# dynext_v1_1.net
KiCad netlist of a schematic drawn in EAGLE
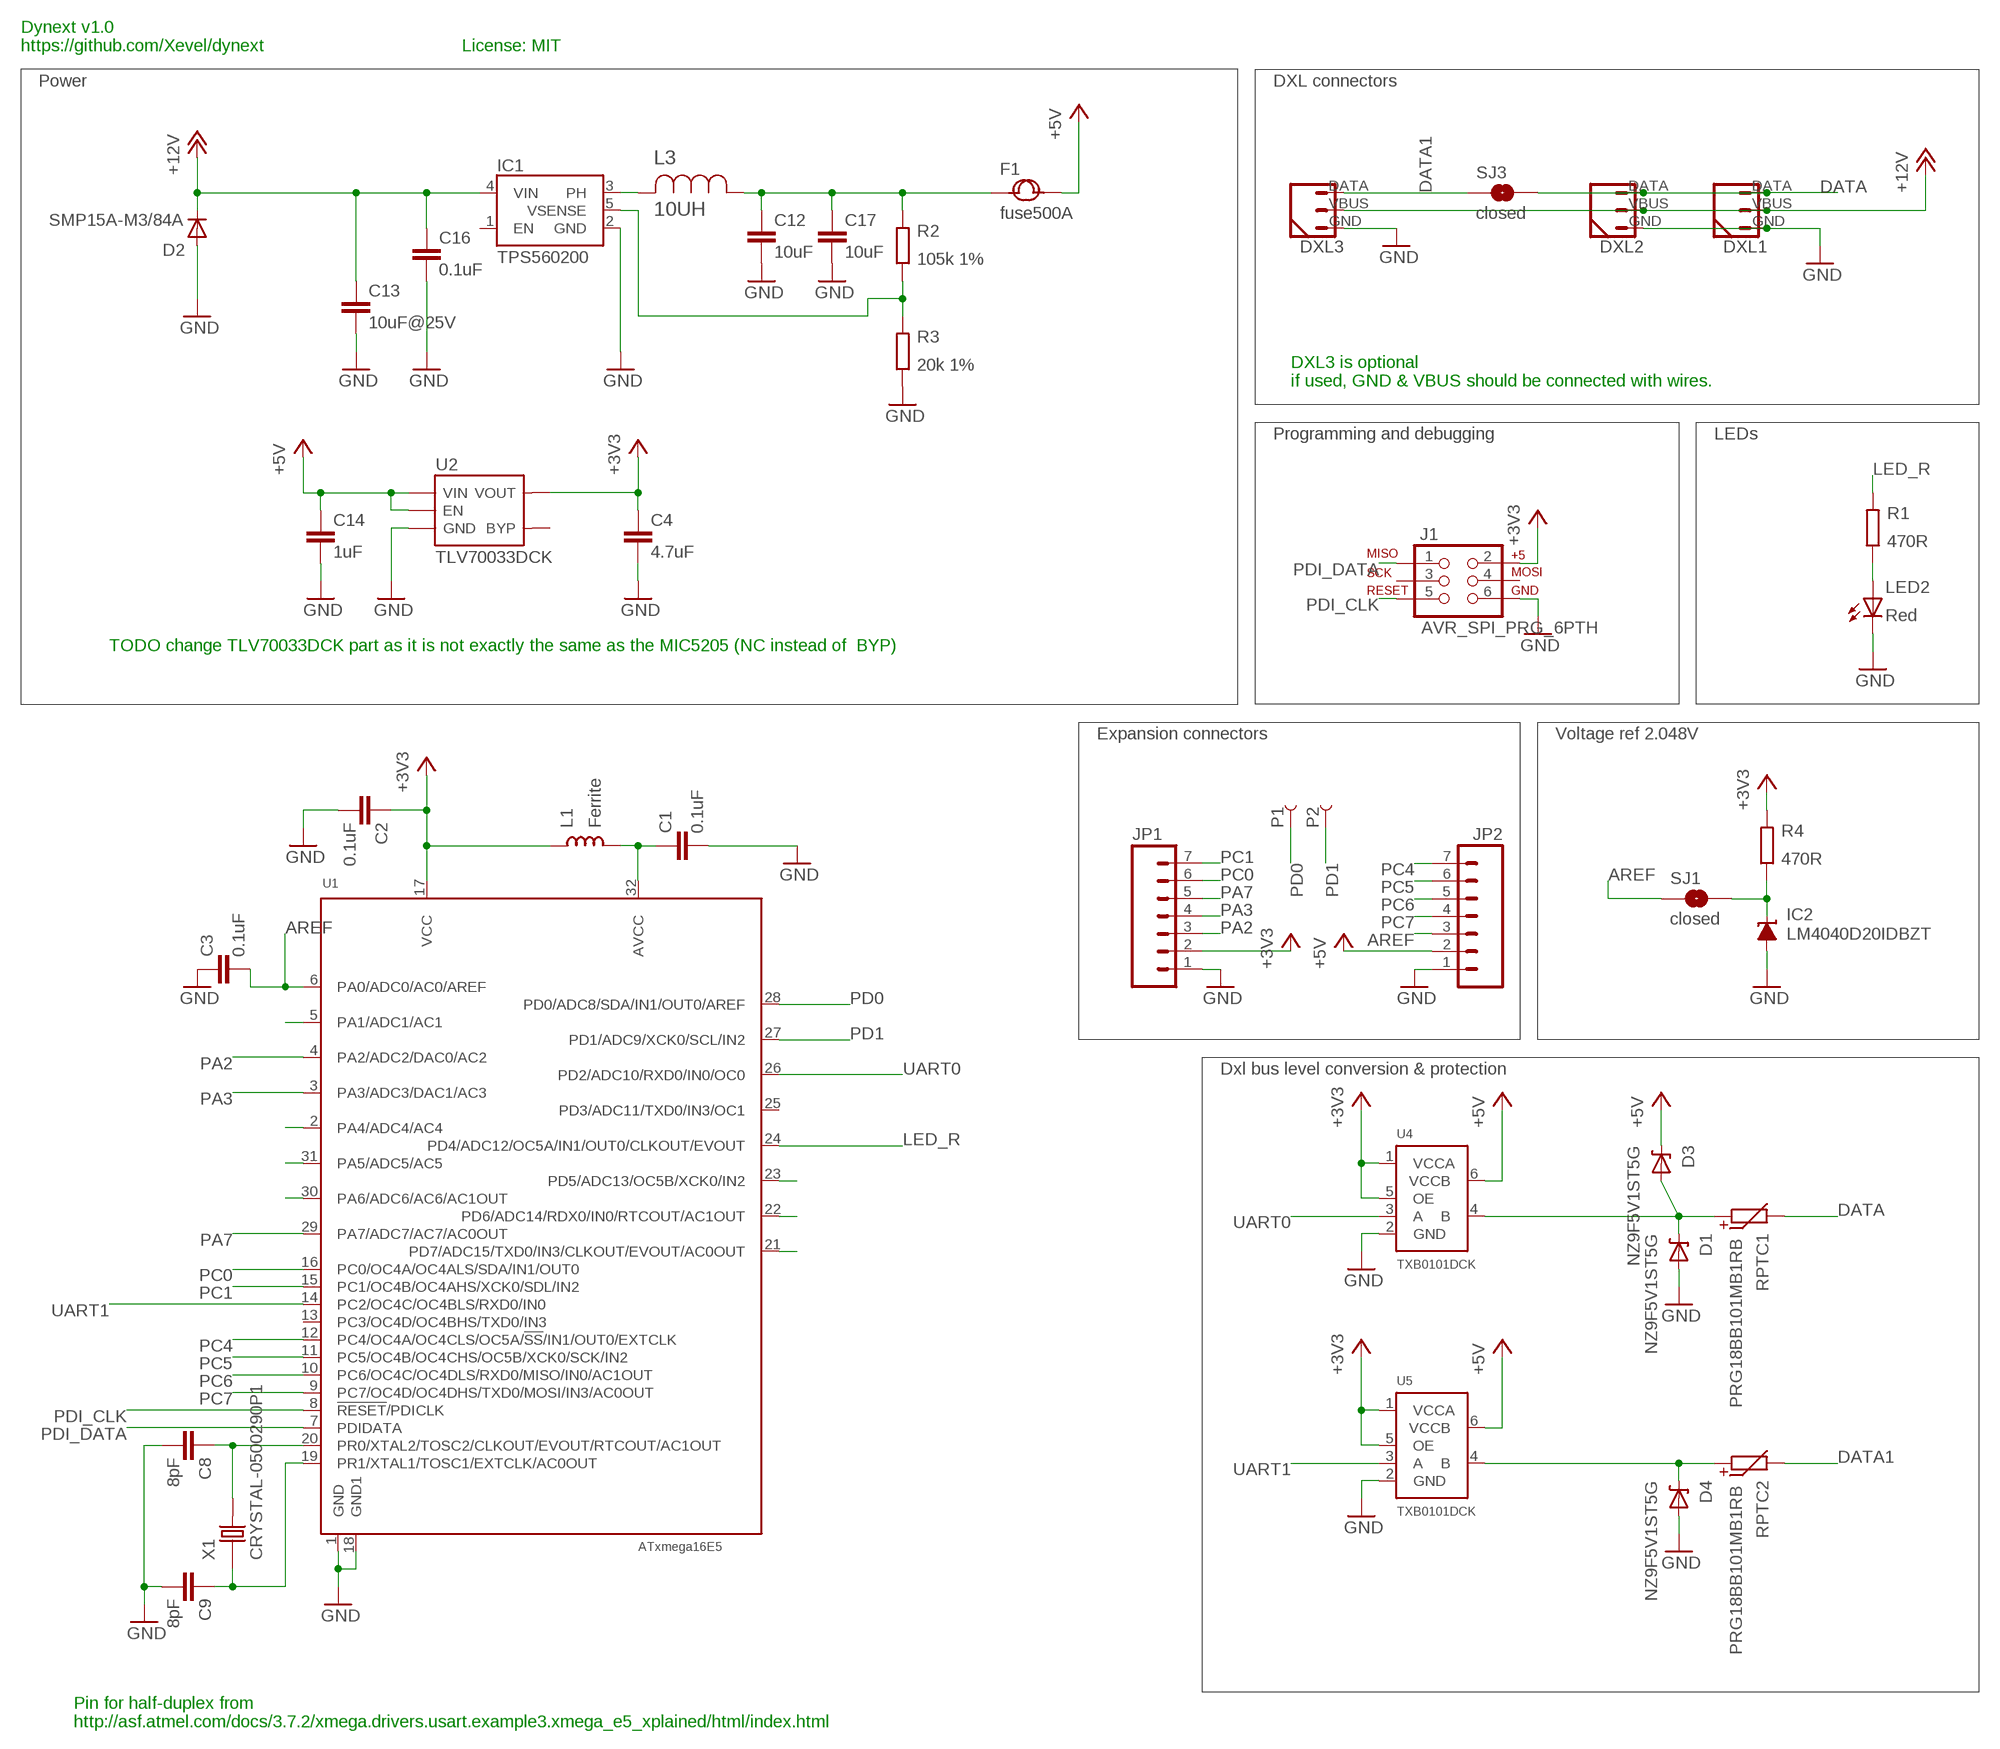
[diagram p0: schematic, sheet 1]

(export (version "E")
  (design (tool "Eeschema 10.0.6"))
  (components
    (comp (ref "C1")
      (value "0.1uF")
      (footprint "eagle-import:0402_N")
      (libsource (lib "eagle-import") (part "C0402"))
    )
    (comp (ref "C2")
      (value "0.1uF")
      (footprint "eagle-import:0402_N")
      (libsource (lib "eagle-import") (part "C0402"))
    )
    (comp (ref "C3")
      (value "0.1uF")
      (footprint "eagle-import:0402_N")
      (libsource (lib "eagle-import") (part "C0402"))
    )
    (comp (ref "C4")
      (value "4.7uF")
      (footprint "eagle-import:0603_N")
      (libsource (lib "eagle-import") (part "C0603"))
    )
    (comp (ref "C8")
      (value "8pF")
      (footprint "eagle-import:0402_N")
      (libsource (lib "eagle-import") (part "C0402"))
    )
    (comp (ref "C9")
      (value "8pF")
      (footprint "eagle-import:0402_N")
      (libsource (lib "eagle-import") (part "C0402"))
    )
    (comp (ref "C12")
      (value "10uF")
      (footprint "eagle-import:0805_N")
      (libsource (lib "eagle-import") (part "C0805"))
    )
    (comp (ref "C13")
      (value "10uF@25V")
      (footprint "eagle-import:0805_N")
      (libsource (lib "eagle-import") (part "C0805"))
    )
    (comp (ref "C14")
      (value "1uF")
      (footprint "eagle-import:0402_N")
      (libsource (lib "eagle-import") (part "C0402"))
    )
    (comp (ref "C16")
      (value "0.1uF")
      (footprint "eagle-import:0402_N")
      (libsource (lib "eagle-import") (part "C0402"))
    )
    (comp (ref "C17")
      (value "10uF")
      (footprint "eagle-import:0805_N")
      (libsource (lib "eagle-import") (part "C0805"))
    )
    (comp (ref "D1")
      (value "NZ9F5V1ST5G")
      (footprint "eagle-import:SOD-923_N")
      (libsource (lib "eagle-import") (part "DIODE_ZENER-923"))
    )
    (comp (ref "D2")
      (value "SMP15A-M3/84A")
      (footprint "eagle-import:DO-220AA")
      (libsource (lib "eagle-import") (part "DIODE-SMP"))
    )
    (comp (ref "D3")
      (value "NZ9F5V1ST5G")
      (footprint "eagle-import:SOD-923_N")
      (libsource (lib "eagle-import") (part "DIODE_ZENER-923"))
    )
    (comp (ref "D4")
      (value "NZ9F5V1ST5G")
      (footprint "eagle-import:SOD-923_N")
      (libsource (lib "eagle-import") (part "DIODE_ZENER-923"))
    )
    (comp (ref "DXL1")
      (value "DYNAMIXEL_3POS-T")
      (footprint "eagle-import:DYNAMIXEL_3POS_TOP")
      (libsource (lib "eagle-import") (part "DYNAMIXEL_3POS-T"))
    )
    (comp (ref "DXL2")
      (value "DYNAMIXEL_3POS-T")
      (footprint "eagle-import:DYNAMIXEL_3POS_TOP")
      (libsource (lib "eagle-import") (part "DYNAMIXEL_3POS-T"))
    )
    (comp (ref "DXL3")
      (value "DYNAMIXEL_3POS-R")
      (footprint "eagle-import:DYNAMIXEL_3POS_RIGHT")
      (libsource (lib "eagle-import") (part "DYNAMIXEL_3POS-R"))
    )
    (comp (ref "F1")
      (value "fuse500A")
      (footprint "eagle-import:F1206")
      (libsource (lib "eagle-import") (part "FUSE-1206"))
    )
    (comp (ref "IC1")
      (value "TPS560200")
      (footprint "eagle-import:SOT-23-5_N")
      (libsource (lib "eagle-import") (part "IC_TPS560200"))
    )
    (comp (ref "IC2")
      (value "LM4040D20IDBZT")
      (footprint "eagle-import:DBZ_R-PDSO-G3")
      (fields (field (name "MPN") "LM4041A12IDBZR"))
      (libsource (lib "eagle-import") (part "LM4041DBZA12"))
    )
    (comp (ref "J1")
      (value "AVR_SPI_PRG_6PTH")
      (footprint "eagle-import:2X3")
      (libsource (lib "eagle-import") (part "AVR_SPI_PRG_6PTH"))
    )
    (comp (ref "JP1")
      (value "M07")
      (footprint "eagle-import:1X07")
      (libsource (lib "eagle-import") (part "M07"))
    )
    (comp (ref "JP2")
      (value "M07")
      (footprint "eagle-import:1X07")
      (libsource (lib "eagle-import") (part "M07"))
    )
    (comp (ref "L1")
      (value "Ferrite")
      (footprint "eagle-import:0603_N")
      (libsource (lib "eagle-import") (part "L0603"))
    )
    (comp (ref "L3")
      (value "10UH")
      (footprint "eagle-import:IND_ELL4XG")
      (fields (field (name "MPN") "ELL4LG100MA"))
      (libsource (lib "eagle-import") (part "ELL-4XG4LG100MA"))
    )
    (comp (ref "LED2")
      (value "Red")
      (footprint "eagle-import:D_0603_N")
      (libsource (lib "eagle-import") (part "LED0603"))
    )
    (comp (ref "P1")
      (value "PIN_SMD_2X2.5")
      (footprint "eagle-import:PIN_SMD_2X2.5")
      (libsource (lib "eagle-import") (part "PIN_SMD_2X2.5"))
    )
    (comp (ref "P2")
      (value "PIN_SMD_2X2.5")
      (footprint "eagle-import:PIN_SMD_2X2.5")
      (libsource (lib "eagle-import") (part "PIN_SMD_2X2.5"))
    )
    (comp (ref "R1")
      (value "470R")
      (footprint "eagle-import:0402_N")
      (libsource (lib "eagle-import") (part "R0402"))
    )
    (comp (ref "R2")
      (value "105k 1%")
      (footprint "eagle-import:0402_N")
      (libsource (lib "eagle-import") (part "R0402"))
    )
    (comp (ref "R3")
      (value "20k 1%")
      (footprint "eagle-import:0402_N")
      (libsource (lib "eagle-import") (part "R0402"))
    )
    (comp (ref "R4")
      (value "470R")
      (footprint "eagle-import:0402_N")
      (libsource (lib "eagle-import") (part "R0402"))
    )
    (comp (ref "RPTC1")
      (value "PRG18BB101MB1RB")
      (footprint "eagle-import:0603_N")
      (libsource (lib "eagle-import") (part "R-PTC0603"))
    )
    (comp (ref "RPTC2")
      (value "PRG18BB101MB1RB")
      (footprint "eagle-import:0603_N")
      (libsource (lib "eagle-import") (part "R-PTC0603"))
    )
    (comp (ref "SJ1")
      (value "closed")
      (footprint "eagle-import:SJ_2S-TRACE2")
      (libsource (lib "eagle-import") (part "SOLDERJUMPER2_TRACE2"))
    )
    (comp (ref "SJ3")
      (value "closed")
      (footprint "eagle-import:SJ_2S-TRACE2")
      (libsource (lib "eagle-import") (part "SOLDERJUMPER2_TRACE2"))
    )
    (comp (ref "U1")
      (value "ATxmega16E5")
      (footprint "eagle-import:QFN-32_50P_L_MOD")
      (libsource (lib "eagle-import") (part "ATXMEGAE5-MU_MOD"))
    )
    (comp (ref "U2")
      (value "TLV70033DCK")
      (footprint "eagle-import:SC70-5")
      (libsource (lib "eagle-import") (part "MIC5205-3.3YM5"))
    )
    (comp (ref "U4")
      (value "TXB0101DCK")
      (footprint "eagle-import:SC70-6")
      (libsource (lib "eagle-import") (part "TXB0101DCK"))
    )
    (comp (ref "U5")
      (value "TXB0101DCK")
      (footprint "eagle-import:SC70-6")
      (libsource (lib "eagle-import") (part "TXB0101DCK"))
    )
    (comp (ref "X1")
      (value "CRYSTAL-0500290P1")
      (footprint "eagle-import:2P-SMD-5.0X3.2")
      (libsource (lib "eagle-import") (part "CRYSTAL-0500290P1"))
    )
  )
  (nets
    (net (code "1") (name "+3V3") (class "Default")
      (node (ref "C2") (pin "1") (pinfunction "1_1") (pintype "passive"))
      (node (ref "C4") (pin "1") (pinfunction "1_1") (pintype "passive"))
      (node (ref "J1") (pin "2") (pinfunction "2_2") (pintype "passive"))
      (node (ref "JP1") (pin "2") (pinfunction "2_2") (pintype "passive"))
      (node (ref "L1") (pin "1") (pinfunction "1_1") (pintype "passive"))
      (node (ref "R4") (pin "2") (pinfunction "2_2") (pintype "passive"))
      (node (ref "U1") (pin "17") (pinfunction "VCC_17") (pintype "bidirectional"))
      (node (ref "U2") (pin "5") (pinfunction "VOUT_5") (pintype "bidirectional"))
      (node (ref "U4") (pin "1") (pinfunction "VCCA_1") (pintype "bidirectional"))
      (node (ref "U4") (pin "5") (pinfunction "OE_5") (pintype "bidirectional"))
      (node (ref "U5") (pin "1") (pinfunction "VCCA_1") (pintype "bidirectional"))
      (node (ref "U5") (pin "5") (pinfunction "OE_5") (pintype "bidirectional"))
    )
    (net (code "2") (name "+5V") (class "Default")
      (node (ref "C14") (pin "1") (pinfunction "1_1") (pintype "passive"))
      (node (ref "D3") (pin "C") (pinfunction "C_C") (pintype "passive"))
      (node (ref "F1") (pin "2") (pinfunction "2_2") (pintype "bidirectional"))
      (node (ref "JP2") (pin "2") (pinfunction "2_2") (pintype "passive"))
      (node (ref "U2") (pin "1") (pinfunction "VIN_1") (pintype "bidirectional"))
      (node (ref "U2") (pin "3") (pinfunction "EN_3") (pintype "bidirectional"))
      (node (ref "U4") (pin "6") (pinfunction "VCCB_6") (pintype "bidirectional"))
      (node (ref "U5") (pin "6") (pinfunction "VCCB_6") (pintype "bidirectional"))
    )
    (net (code "3") (name "+12V") (class "Default")
      (node (ref "C13") (pin "1") (pinfunction "1_1") (pintype "passive"))
      (node (ref "C16") (pin "1") (pinfunction "1_1") (pintype "passive"))
      (node (ref "D2") (pin "C") (pinfunction "C_C") (pintype "passive"))
      (node (ref "DXL1") (pin "VBUS") (pinfunction "2_VBUS") (pintype "bidirectional"))
      (node (ref "DXL2") (pin "VBUS") (pinfunction "2_VBUS") (pintype "bidirectional"))
      (node (ref "DXL3") (pin "VBUS") (pinfunction "2_VBUS") (pintype "bidirectional"))
      (node (ref "IC1") (pin "4") (pinfunction "VIN_4") (pintype "bidirectional"))
    )
    (net (code "4") (name "/AREF") (class "Default")
      (node (ref "C3") (pin "2") (pinfunction "2_2") (pintype "passive"))
      (node (ref "JP2") (pin "3") (pinfunction "3_3") (pintype "passive"))
      (node (ref "SJ1") (pin "1") (pinfunction "1_1") (pintype "passive"))
      (node (ref "U1") (pin "6") (pinfunction "PA0/ADC0/AC0/AREF_6") (pintype "bidirectional"))
    )
    (net (code "5") (name "/DATA") (class "Default")
      (node (ref "DXL1") (pin "DATA") (pinfunction "3_DATA") (pintype "bidirectional"))
      (node (ref "DXL2") (pin "DATA") (pinfunction "3_DATA") (pintype "bidirectional"))
      (node (ref "RPTC1") (pin "2") (pinfunction "2_2") (pintype "passive"))
      (node (ref "SJ3") (pin "2") (pinfunction "2_2") (pintype "passive"))
    )
    (net (code "6") (name "/DATA1") (class "Default")
      (node (ref "DXL3") (pin "DATA") (pinfunction "3_DATA") (pintype "bidirectional"))
      (node (ref "RPTC2") (pin "2") (pinfunction "2_2") (pintype "passive"))
      (node (ref "SJ3") (pin "1") (pinfunction "1_1") (pintype "passive"))
    )
    (net (code "7") (name "/LED_R") (class "Default")
      (node (ref "R1") (pin "2") (pinfunction "2_2") (pintype "passive"))
      (node (ref "U1") (pin "24") (pinfunction "PD4/ADC12/OC5A/IN1/OUT0/CLKOUT/EVOUT_24") (pintype "bidirectional"))
    )
    (net (code "8") (name "/PA2") (class "Default")
      (node (ref "JP1") (pin "3") (pinfunction "3_3") (pintype "passive"))
      (node (ref "U1") (pin "4") (pinfunction "PA2/ADC2/DAC0/AC2_4") (pintype "bidirectional"))
    )
    (net (code "9") (name "/PA3") (class "Default")
      (node (ref "JP1") (pin "4") (pinfunction "4_4") (pintype "passive"))
      (node (ref "U1") (pin "3") (pinfunction "PA3/ADC3/DAC1/AC3_3") (pintype "bidirectional"))
    )
    (net (code "10") (name "/PA7") (class "Default")
      (node (ref "JP1") (pin "5") (pinfunction "5_5") (pintype "passive"))
      (node (ref "U1") (pin "29") (pinfunction "PA7/ADC7/AC7/AC0OUT_29") (pintype "bidirectional"))
    )
    (net (code "11") (name "/PC0") (class "Default")
      (node (ref "JP1") (pin "6") (pinfunction "6_6") (pintype "passive"))
      (node (ref "U1") (pin "16") (pinfunction "PC0/OC4A/OC4ALS/SDA/IN1/OUT0_16") (pintype "bidirectional"))
    )
    (net (code "12") (name "/PC1") (class "Default")
      (node (ref "JP1") (pin "7") (pinfunction "7_7") (pintype "passive"))
      (node (ref "U1") (pin "15") (pinfunction "PC1/OC4B/OC4AHS/XCK0/SDL/IN2_15") (pintype "bidirectional"))
    )
    (net (code "13") (name "/PC4") (class "Default")
      (node (ref "JP2") (pin "7") (pinfunction "7_7") (pintype "passive"))
      (node (ref "U1") (pin "12") (pinfunction "PC4/OC4A/OC4CLS/OC5A/~{SS}/IN1/OUT0/EXTCLK_12") (pintype "bidirectional"))
    )
    (net (code "14") (name "/PC5") (class "Default")
      (node (ref "JP2") (pin "6") (pinfunction "6_6") (pintype "passive"))
      (node (ref "U1") (pin "11") (pinfunction "PC5/OC4B/OC4CHS/OC5B/XCK0/SCK/IN2_11") (pintype "bidirectional"))
    )
    (net (code "15") (name "/PC6") (class "Default")
      (node (ref "JP2") (pin "5") (pinfunction "5_5") (pintype "passive"))
      (node (ref "U1") (pin "10") (pinfunction "PC6/OC4C/OC4DLS/RXD0/MISO/IN0/AC1OUT_10") (pintype "bidirectional"))
    )
    (net (code "16") (name "/PC7") (class "Default")
      (node (ref "JP2") (pin "4") (pinfunction "4_4") (pintype "passive"))
      (node (ref "U1") (pin "9") (pinfunction "PC7/OC4D/OC4DHS/TXD0/MOSI/IN3/AC0OUT_9") (pintype "bidirectional"))
    )
    (net (code "17") (name "/PD0") (class "Default")
      (node (ref "P1") (pin "PIN") (pinfunction "1_PIN") (pintype "bidirectional"))
      (node (ref "U1") (pin "28") (pinfunction "PD0/ADC8/SDA/IN1/OUT0/AREF_28") (pintype "bidirectional"))
    )
    (net (code "18") (name "/PD1") (class "Default")
      (node (ref "P2") (pin "PIN") (pinfunction "1_PIN") (pintype "bidirectional"))
      (node (ref "U1") (pin "27") (pinfunction "PD1/ADC9/XCK0/SCL/IN2_27") (pintype "bidirectional"))
    )
    (net (code "19") (name "/PDI_CLK") (class "Default")
      (node (ref "J1") (pin "5") (pinfunction "5_5") (pintype "passive"))
      (node (ref "U1") (pin "8") (pinfunction "~{RESET}/PDICLK_8") (pintype "bidirectional"))
    )
    (net (code "20") (name "/PDI_DATA") (class "Default")
      (node (ref "J1") (pin "1") (pinfunction "1_1") (pintype "passive"))
      (node (ref "U1") (pin "7") (pinfunction "PDIDATA_7") (pintype "bidirectional"))
    )
    (net (code "21") (name "/UART0") (class "Default")
      (node (ref "U1") (pin "26") (pinfunction "PD2/ADC10/RXD0/IN0/OC0_26") (pintype "bidirectional"))
      (node (ref "U4") (pin "3") (pinfunction "A_3") (pintype "bidirectional"))
    )
    (net (code "22") (name "/UART1") (class "Default")
      (node (ref "U1") (pin "14") (pinfunction "PC2/OC4C/OC4BLS/RXD0/IN0_14") (pintype "bidirectional"))
      (node (ref "U5") (pin "3") (pinfunction "A_3") (pintype "bidirectional"))
    )
    (net (code "23") (name "GND") (class "Default")
      (node (ref "C1") (pin "2") (pinfunction "2_2") (pintype "passive"))
      (node (ref "C12") (pin "2") (pinfunction "2_2") (pintype "passive"))
      (node (ref "C13") (pin "2") (pinfunction "2_2") (pintype "passive"))
      (node (ref "C14") (pin "2") (pinfunction "2_2") (pintype "passive"))
      (node (ref "C16") (pin "2") (pinfunction "2_2") (pintype "passive"))
      (node (ref "C17") (pin "2") (pinfunction "2_2") (pintype "passive"))
      (node (ref "C2") (pin "2") (pinfunction "2_2") (pintype "passive"))
      (node (ref "C3") (pin "1") (pinfunction "1_1") (pintype "passive"))
      (node (ref "C4") (pin "2") (pinfunction "2_2") (pintype "passive"))
      (node (ref "C8") (pin "2") (pinfunction "2_2") (pintype "passive"))
      (node (ref "C9") (pin "2") (pinfunction "2_2") (pintype "passive"))
      (node (ref "D1") (pin "A") (pinfunction "A_A") (pintype "passive"))
      (node (ref "D2") (pin "A") (pinfunction "A_A") (pintype "passive"))
      (node (ref "D4") (pin "A") (pinfunction "A_A") (pintype "passive"))
      (node (ref "DXL1") (pin "GND") (pinfunction "1_GND") (pintype "bidirectional"))
      (node (ref "DXL2") (pin "GND") (pinfunction "1_GND") (pintype "bidirectional"))
      (node (ref "DXL3") (pin "GND") (pinfunction "1_GND") (pintype "bidirectional"))
      (node (ref "IC1") (pin "2") (pinfunction "GND_2") (pintype "input"))
      (node (ref "IC2") (pin "2") (pinfunction "A_2") (pintype "passive"))
      (node (ref "J1") (pin "6") (pinfunction "6_6") (pintype "passive"))
      (node (ref "JP1") (pin "1") (pinfunction "1_1") (pintype "passive"))
      (node (ref "JP2") (pin "1") (pinfunction "1_1") (pintype "passive"))
      (node (ref "LED2") (pin "C") (pinfunction "C_C") (pintype "passive"))
      (node (ref "R3") (pin "1") (pinfunction "1_1") (pintype "passive"))
      (node (ref "U1") (pin "1") (pinfunction "GND_1") (pintype "bidirectional"))
      (node (ref "U1") (pin "18") (pinfunction "GND1_18") (pintype "bidirectional"))
      (node (ref "U2") (pin "2") (pinfunction "GND_2") (pintype "bidirectional"))
      (node (ref "U4") (pin "2") (pinfunction "GND_2") (pintype "bidirectional"))
      (node (ref "U5") (pin "2") (pinfunction "GND_2") (pintype "bidirectional"))
    )
    (net (code "24") (name "Net-(C12-Pad1)") (class "Default")
      (node (ref "C12") (pin "1") (pinfunction "1_1") (pintype "passive"))
      (node (ref "C17") (pin "1") (pinfunction "1_1") (pintype "passive"))
      (node (ref "F1") (pin "1") (pinfunction "1_1") (pintype "bidirectional"))
      (node (ref "L3") (pin "1") (pinfunction "1_1") (pintype "passive"))
      (node (ref "R2") (pin "2") (pinfunction "2_2") (pintype "passive"))
    )
    (net (code "25") (name "Net-(IC1-PH)") (class "Default")
      (node (ref "IC1") (pin "3") (pinfunction "PH_3") (pintype "bidirectional"))
      (node (ref "L3") (pin "2") (pinfunction "2_2") (pintype "passive"))
    )
    (net (code "26") (name "Net-(IC1-VSENSE)") (class "Default")
      (node (ref "IC1") (pin "5") (pinfunction "VSENSE_5") (pintype "bidirectional"))
      (node (ref "R2") (pin "1") (pinfunction "1_1") (pintype "passive"))
      (node (ref "R3") (pin "2") (pinfunction "2_2") (pintype "passive"))
    )
    (net (code "27") (name "Net-(IC2-C)") (class "Default")
      (node (ref "IC2") (pin "1") (pinfunction "C_1") (pintype "passive"))
      (node (ref "R4") (pin "1") (pinfunction "1_1") (pintype "passive"))
      (node (ref "SJ1") (pin "2") (pinfunction "2_2") (pintype "passive"))
    )
    (net (code "28") (name "Net-(LED2-PadA)") (class "Default")
      (node (ref "LED2") (pin "A") (pinfunction "A_A") (pintype "passive"))
      (node (ref "R1") (pin "1") (pinfunction "1_1") (pintype "passive"))
    )
    (net (code "29") (name "Net-(U1-AVCC)") (class "Default")
      (node (ref "C1") (pin "1") (pinfunction "1_1") (pintype "passive"))
      (node (ref "L1") (pin "2") (pinfunction "2_2") (pintype "passive"))
      (node (ref "U1") (pin "32") (pinfunction "AVCC_32") (pintype "bidirectional"))
    )
    (net (code "30") (name "Net-(U1-PR0{slash}XTAL2{slash}TOSC2{slash}CLKOUT{slash}EVOUT{slash}RTCOUT{slash}AC1OUT)") (class "Default")
      (node (ref "C8") (pin "1") (pinfunction "1_1") (pintype "passive"))
      (node (ref "U1") (pin "20") (pinfunction "PR0/XTAL2/TOSC2/CLKOUT/EVOUT/RTCOUT/AC1OUT_20") (pintype "bidirectional"))
      (node (ref "X1") (pin "2") (pinfunction "2_2") (pintype "passive"))
    )
    (net (code "31") (name "Net-(U1-PR1{slash}XTAL1{slash}TOSC1{slash}EXTCLK{slash}AC0OUT)") (class "Default")
      (node (ref "C9") (pin "1") (pinfunction "1_1") (pintype "passive"))
      (node (ref "U1") (pin "19") (pinfunction "PR1/XTAL1/TOSC1/EXTCLK/AC0OUT_19") (pintype "bidirectional"))
      (node (ref "X1") (pin "1") (pinfunction "1_1") (pintype "passive"))
    )
    (net (code "32") (name "Net-(U4-B)") (class "Default")
      (node (ref "D1") (pin "C") (pinfunction "C_C") (pintype "passive"))
      (node (ref "D3") (pin "A") (pinfunction "A_A") (pintype "passive"))
      (node (ref "RPTC1") (pin "1") (pinfunction "1_1") (pintype "passive"))
      (node (ref "U4") (pin "4") (pinfunction "B_4") (pintype "bidirectional"))
    )
    (net (code "33") (name "Net-(U5-B)") (class "Default")
      (node (ref "D4") (pin "C") (pinfunction "C_C") (pintype "passive"))
      (node (ref "RPTC2") (pin "1") (pinfunction "1_1") (pintype "passive"))
      (node (ref "U5") (pin "4") (pinfunction "B_4") (pintype "bidirectional"))
    )
    (net (code "34") (name "unconnected-(IC1-EN-Pad1)") (class "Default")
      (node (ref "IC1") (pin "1") (pinfunction "EN_1") (pintype "input"))
    )
    (net (code "35") (name "unconnected-(J1-Pad3)") (class "Default")
      (node (ref "J1") (pin "3") (pinfunction "3_3") (pintype "passive"))
    )
    (net (code "36") (name "unconnected-(J1-Pad4)") (class "Default")
      (node (ref "J1") (pin "4") (pinfunction "4_4") (pintype "passive"))
    )
    (net (code "37") (name "unconnected-(U1-PA1{slash}ADC1{slash}AC1-Pad5)") (class "Default")
      (node (ref "U1") (pin "5") (pinfunction "PA1/ADC1/AC1_5") (pintype "bidirectional"))
    )
    (net (code "38") (name "unconnected-(U1-PA4{slash}ADC4{slash}AC4-Pad2)") (class "Default")
      (node (ref "U1") (pin "2") (pinfunction "PA4/ADC4/AC4_2") (pintype "bidirectional"))
    )
    (net (code "39") (name "unconnected-(U1-PA5{slash}ADC5{slash}AC5-Pad31)") (class "Default")
      (node (ref "U1") (pin "31") (pinfunction "PA5/ADC5/AC5_31") (pintype "bidirectional"))
    )
    (net (code "40") (name "unconnected-(U1-PA6{slash}ADC6{slash}AC6{slash}AC1OUT-Pad30)") (class "Default")
      (node (ref "U1") (pin "30") (pinfunction "PA6/ADC6/AC6/AC1OUT_30") (pintype "bidirectional"))
    )
    (net (code "41") (name "unconnected-(U1-PC3{slash}OC4D{slash}OC4BHS{slash}TXD0{slash}IN3-Pad13)") (class "Default")
      (node (ref "U1") (pin "13") (pinfunction "PC3/OC4D/OC4BHS/TXD0/IN3_13") (pintype "bidirectional"))
    )
    (net (code "42") (name "unconnected-(U1-PD3{slash}ADC11{slash}TXD0{slash}IN3{slash}OC1-Pad25)") (class "Default")
      (node (ref "U1") (pin "25") (pinfunction "PD3/ADC11/TXD0/IN3/OC1_25") (pintype "bidirectional"))
    )
    (net (code "43") (name "unconnected-(U1-PD5{slash}ADC13{slash}OC5B{slash}XCK0{slash}IN2-Pad23)") (class "Default")
      (node (ref "U1") (pin "23") (pinfunction "PD5/ADC13/OC5B/XCK0/IN2_23") (pintype "bidirectional"))
    )
    (net (code "44") (name "unconnected-(U1-PD6{slash}ADC14{slash}RDX0{slash}IN0{slash}RTCOUT{slash}AC1OUT-Pad22)") (class "Default")
      (node (ref "U1") (pin "22") (pinfunction "PD6/ADC14/RDX0/IN0/RTCOUT/AC1OUT_22") (pintype "bidirectional"))
    )
    (net (code "45") (name "unconnected-(U1-PD7{slash}ADC15{slash}TXD0{slash}IN3{slash}CLKOUT{slash}EVOUT{slash}AC0OUT-Pad21)") (class "Default")
      (node (ref "U1") (pin "21") (pinfunction "PD7/ADC15/TXD0/IN3/CLKOUT/EVOUT/AC0OUT_21") (pintype "bidirectional"))
    )
    (net (code "46") (name "unconnected-(U2-BYP-Pad4)") (class "Default")
      (node (ref "U2") (pin "4") (pinfunction "BYP_4") (pintype "bidirectional"))
    )
  )
)
